# calibration-rig.net
KiCad netlist of a schematic drawn in EAGLE
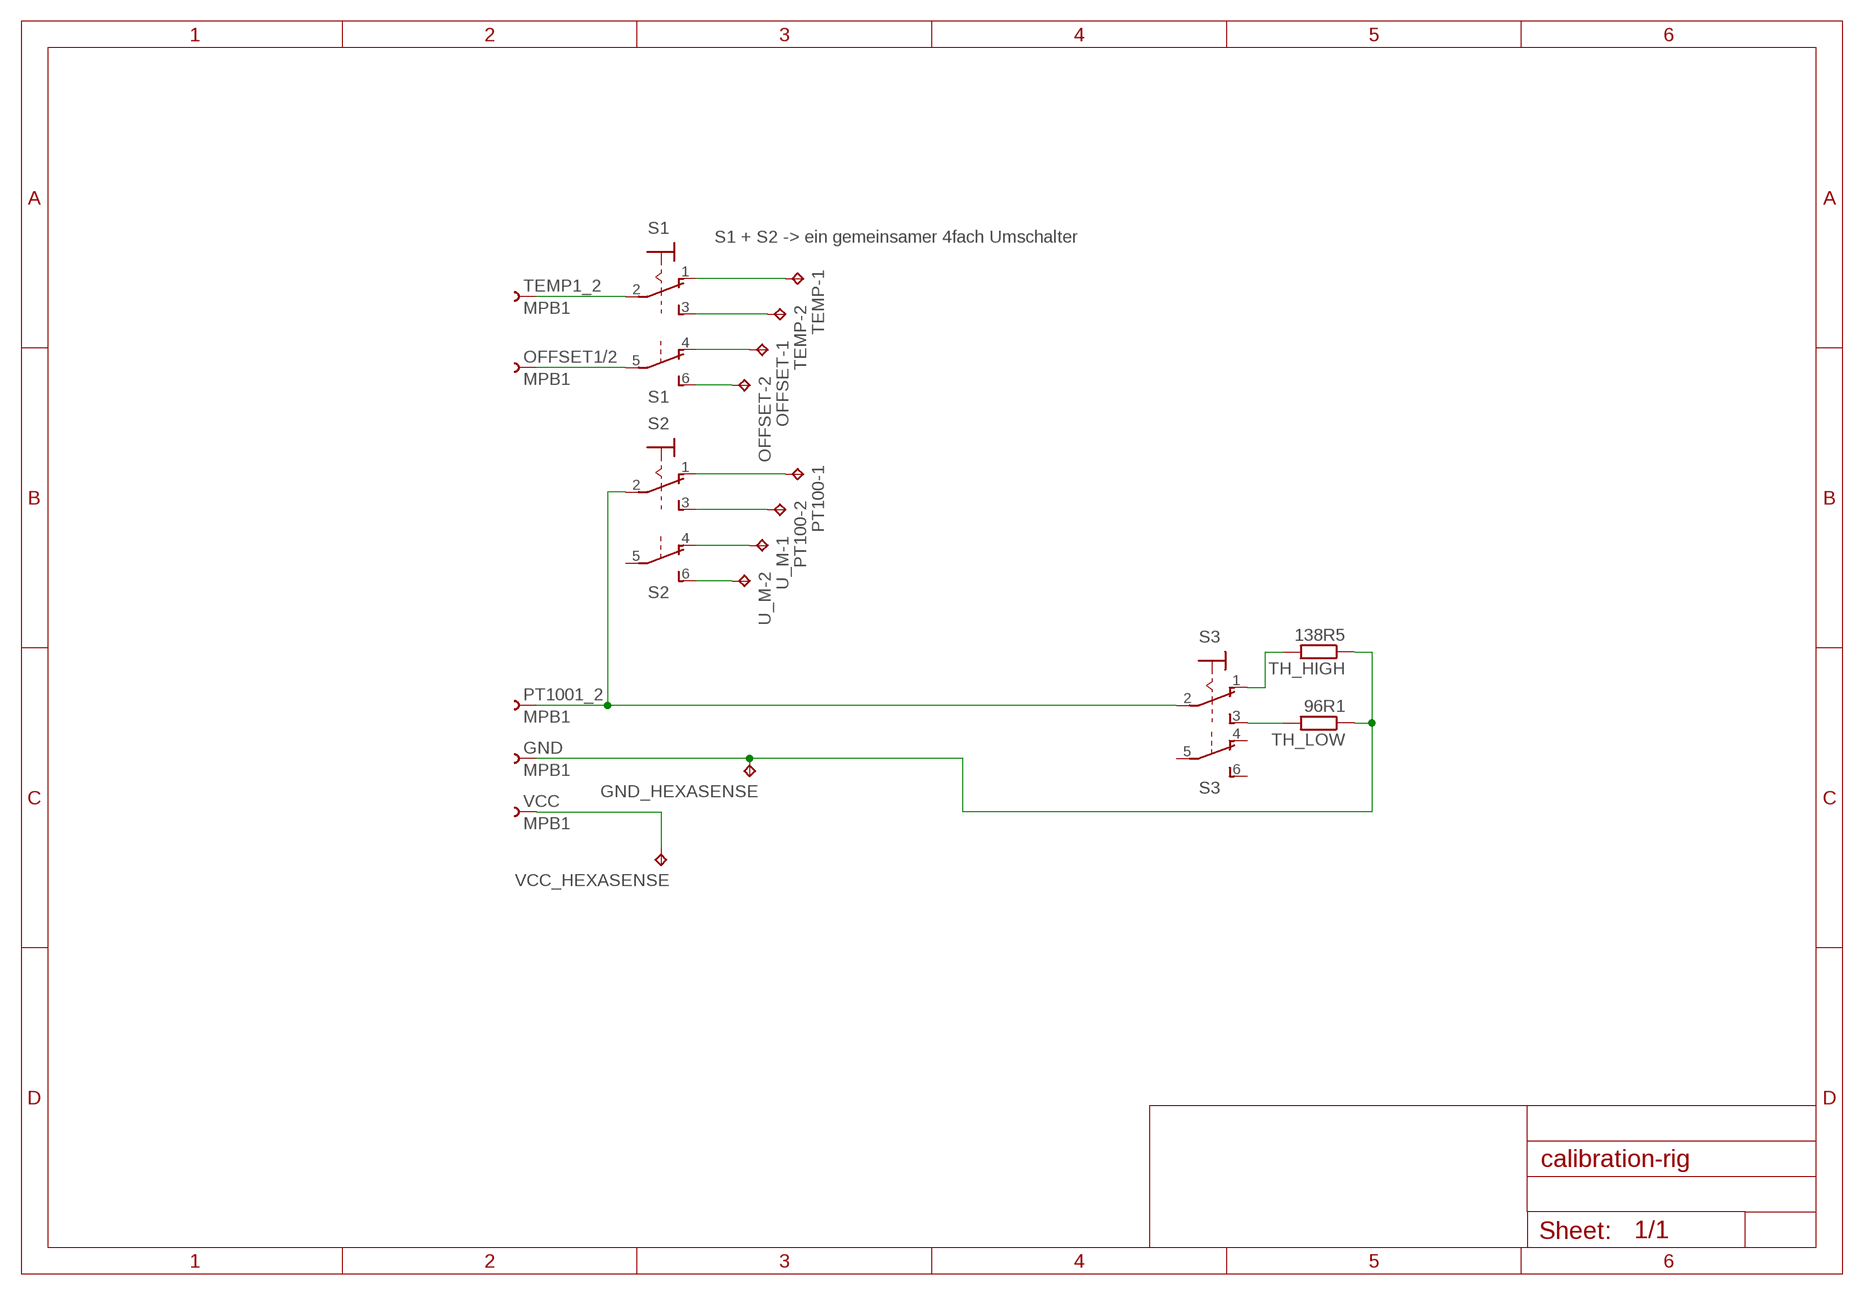
[diagram p0: schematic, sheet 1]

(export (version "E")
  (design (tool "Eeschema 10.0.6"))
  (components
    (comp (ref "GND")
      (value "MPB1")
      (footprint "eagle-import:MPB1")
      (fields (field (name "MF") "FARNELL") (field (name "MPN") "MPB1 BLACK"))
      (libsource (lib "eagle-import") (part "MPB1"))
    )
    (comp (ref "GND_HEXASENSE")
      (value "TPB1,27")
      (footprint "eagle-import:B1,27")
      (libsource (lib "eagle-import") (part "TPB1,27"))
    )
    (comp (ref "OFFSET-1")
      (value "TPB1,27")
      (footprint "eagle-import:B1,27")
      (libsource (lib "eagle-import") (part "TPB1,27"))
    )
    (comp (ref "OFFSET-2")
      (value "TPB1,27")
      (footprint "eagle-import:B1,27")
      (libsource (lib "eagle-import") (part "TPB1,27"))
    )
    (comp (ref "OFFSET1/2")
      (value "MPB1")
      (footprint "eagle-import:MPB1")
      (fields (field (name "MF") "FARNELL") (field (name "MPN") "MPB1 BLACK"))
      (libsource (lib "eagle-import") (part "MPB1"))
    )
    (comp (ref "PT100-1")
      (value "TPB1,27")
      (footprint "eagle-import:B1,27")
      (libsource (lib "eagle-import") (part "TPB1,27"))
    )
    (comp (ref "PT100-2")
      (value "TPB1,27")
      (footprint "eagle-import:B1,27")
      (libsource (lib "eagle-import") (part "TPB1,27"))
    )
    (comp (ref "PT1001_2")
      (value "MPB1")
      (footprint "eagle-import:MPB1")
      (fields (field (name "MF") "FARNELL") (field (name "MPN") "MPB1 BLACK"))
      (libsource (lib "eagle-import") (part "MPB1"))
    )
    (comp (ref "S1")
      (value "M9040P2")
      (footprint "eagle-import:M9040P2")
      (libsource (lib "eagle-import") (part "M9040P2"))
    )
    (comp (ref "S2")
      (value "M9040P2")
      (footprint "eagle-import:M9040P2")
      (libsource (lib "eagle-import") (part "M9040P2"))
    )
    (comp (ref "S3")
      (value "M9040P2")
      (footprint "eagle-import:M9040P2")
      (libsource (lib "eagle-import") (part "M9040P2"))
    )
    (comp (ref "TEMP-1")
      (value "TPB1,27")
      (footprint "eagle-import:B1,27")
      (libsource (lib "eagle-import") (part "TPB1,27"))
    )
    (comp (ref "TEMP-2")
      (value "TPB1,27")
      (footprint "eagle-import:B1,27")
      (libsource (lib "eagle-import") (part "TPB1,27"))
    )
    (comp (ref "TEMP1_2")
      (value "MPB1")
      (footprint "eagle-import:MPB1")
      (fields (field (name "MF") "FARNELL") (field (name "MPN") "MPB1 BLACK"))
      (libsource (lib "eagle-import") (part "MPB1"))
    )
    (comp (ref "TH_HIGH")
      (value "138R5")
      (footprint "eagle-import:0207_10")
      (libsource (lib "eagle-import") (part "R-EU_0207/10"))
    )
    (comp (ref "TH_LOW")
      (value "96R1")
      (footprint "eagle-import:0207_10")
      (libsource (lib "eagle-import") (part "R-EU_0207/10"))
    )
    (comp (ref "U_M-1")
      (value "TPB1,27")
      (footprint "eagle-import:B1,27")
      (libsource (lib "eagle-import") (part "TPB1,27"))
    )
    (comp (ref "U_M-2")
      (value "TPB1,27")
      (footprint "eagle-import:B1,27")
      (libsource (lib "eagle-import") (part "TPB1,27"))
    )
    (comp (ref "VCC")
      (value "MPB1")
      (footprint "eagle-import:MPB1")
      (fields (field (name "MF") "FARNELL") (field (name "MPN") "MPB1 BLACK"))
      (libsource (lib "eagle-import") (part "MPB1"))
    )
    (comp (ref "VCC_HEXASENSE")
      (value "TPB1,27")
      (footprint "eagle-import:B1,27")
      (libsource (lib "eagle-import") (part "TPB1,27"))
    )
  )
  (nets
    (net (code "1") (name "Net-(GND-1-Pad1@1)") (class "Default")
      (node (ref "GND") (pin "1") (pinfunction "1_1") (pintype "passive"))
      (node (ref "GND") (pin "1@1") (pinfunction "1_1@1") (pintype "passive"))
      (node (ref "GND_HEXASENSE") (pin "TP") (pinfunction "TP_TP") (pintype "input"))
      (node (ref "TH_HIGH") (pin "1") (pinfunction "1_1") (pintype "passive"))
      (node (ref "TH_LOW") (pin "1") (pinfunction "1_1") (pintype "passive"))
    )
    (net (code "2") (name "Net-(S1A-O)") (class "Default")
      (node (ref "S1") (pin "1") (pinfunction "O_1") (pintype "passive"))
      (node (ref "TEMP-1") (pin "TP") (pinfunction "TP_TP") (pintype "input"))
    )
    (net (code "3") (name "Net-(S1A-P)") (class "Default")
      (node (ref "S1") (pin "2") (pinfunction "P_2") (pintype "passive"))
      (node (ref "TEMP1_2") (pin "1") (pinfunction "1_1") (pintype "passive"))
      (node (ref "TEMP1_2") (pin "1@1") (pinfunction "1_1@1") (pintype "passive"))
    )
    (net (code "4") (name "Net-(S1A-S)") (class "Default")
      (node (ref "S1") (pin "3") (pinfunction "S_3") (pintype "passive"))
      (node (ref "TEMP-2") (pin "TP") (pinfunction "TP_TP") (pintype "input"))
    )
    (net (code "5") (name "Net-(S1B-O)") (class "Default")
      (node (ref "OFFSET-1") (pin "TP") (pinfunction "TP_TP") (pintype "input"))
      (node (ref "S1") (pin "4") (pinfunction "O_4") (pintype "passive"))
    )
    (net (code "6") (name "Net-(S1B-P)") (class "Default")
      (node (ref "OFFSET1/2") (pin "1") (pinfunction "1_1") (pintype "passive"))
      (node (ref "OFFSET1/2") (pin "1@1") (pinfunction "1_1@1") (pintype "passive"))
      (node (ref "S1") (pin "5") (pinfunction "P_5") (pintype "passive"))
    )
    (net (code "7") (name "Net-(S1B-S)") (class "Default")
      (node (ref "OFFSET-2") (pin "TP") (pinfunction "TP_TP") (pintype "input"))
      (node (ref "S1") (pin "6") (pinfunction "S_6") (pintype "passive"))
    )
    (net (code "8") (name "Net-(S2A-O)") (class "Default")
      (node (ref "PT100-1") (pin "TP") (pinfunction "TP_TP") (pintype "input"))
      (node (ref "S2") (pin "1") (pinfunction "O_1") (pintype "passive"))
    )
    (net (code "9") (name "Net-(S2A-P)") (class "Default")
      (node (ref "PT1001_2") (pin "1") (pinfunction "1_1") (pintype "passive"))
      (node (ref "PT1001_2") (pin "1@1") (pinfunction "1_1@1") (pintype "passive"))
      (node (ref "S2") (pin "2") (pinfunction "P_2") (pintype "passive"))
      (node (ref "S3") (pin "2") (pinfunction "P_2") (pintype "passive"))
    )
    (net (code "10") (name "Net-(S2A-S)") (class "Default")
      (node (ref "PT100-2") (pin "TP") (pinfunction "TP_TP") (pintype "input"))
      (node (ref "S2") (pin "3") (pinfunction "S_3") (pintype "passive"))
    )
    (net (code "11") (name "Net-(S2B-O)") (class "Default")
      (node (ref "S2") (pin "4") (pinfunction "O_4") (pintype "passive"))
      (node (ref "U_M-1") (pin "TP") (pinfunction "TP_TP") (pintype "input"))
    )
    (net (code "12") (name "Net-(S2B-S)") (class "Default")
      (node (ref "S2") (pin "6") (pinfunction "S_6") (pintype "passive"))
      (node (ref "U_M-2") (pin "TP") (pinfunction "TP_TP") (pintype "input"))
    )
    (net (code "13") (name "Net-(S3A-O)") (class "Default")
      (node (ref "S3") (pin "1") (pinfunction "O_1") (pintype "passive"))
      (node (ref "TH_HIGH") (pin "2") (pinfunction "2_2") (pintype "passive"))
    )
    (net (code "14") (name "Net-(S3A-S)") (class "Default")
      (node (ref "S3") (pin "3") (pinfunction "S_3") (pintype "passive"))
      (node (ref "TH_LOW") (pin "2") (pinfunction "2_2") (pintype "passive"))
    )
    (net (code "15") (name "Net-(VCC-1-Pad1@1)") (class "Default")
      (node (ref "VCC") (pin "1") (pinfunction "1_1") (pintype "passive"))
      (node (ref "VCC") (pin "1@1") (pinfunction "1_1@1") (pintype "passive"))
      (node (ref "VCC_HEXASENSE") (pin "TP") (pinfunction "TP_TP") (pintype "input"))
    )
    (net (code "16") (name "unconnected-(S2B-P-Pad5)") (class "Default")
      (node (ref "S2") (pin "5") (pinfunction "P_5") (pintype "passive"))
    )
    (net (code "17") (name "unconnected-(S3B-O-Pad4)") (class "Default")
      (node (ref "S3") (pin "4") (pinfunction "O_4") (pintype "passive"))
    )
    (net (code "18") (name "unconnected-(S3B-P-Pad5)") (class "Default")
      (node (ref "S3") (pin "5") (pinfunction "P_5") (pintype "passive"))
    )
    (net (code "19") (name "unconnected-(S3B-S-Pad6)") (class "Default")
      (node (ref "S3") (pin "6") (pinfunction "S_6") (pintype "passive"))
    )
  )
)
